# Sheet1.net
KiCad netlist of a schematic drawn in Altium Designer
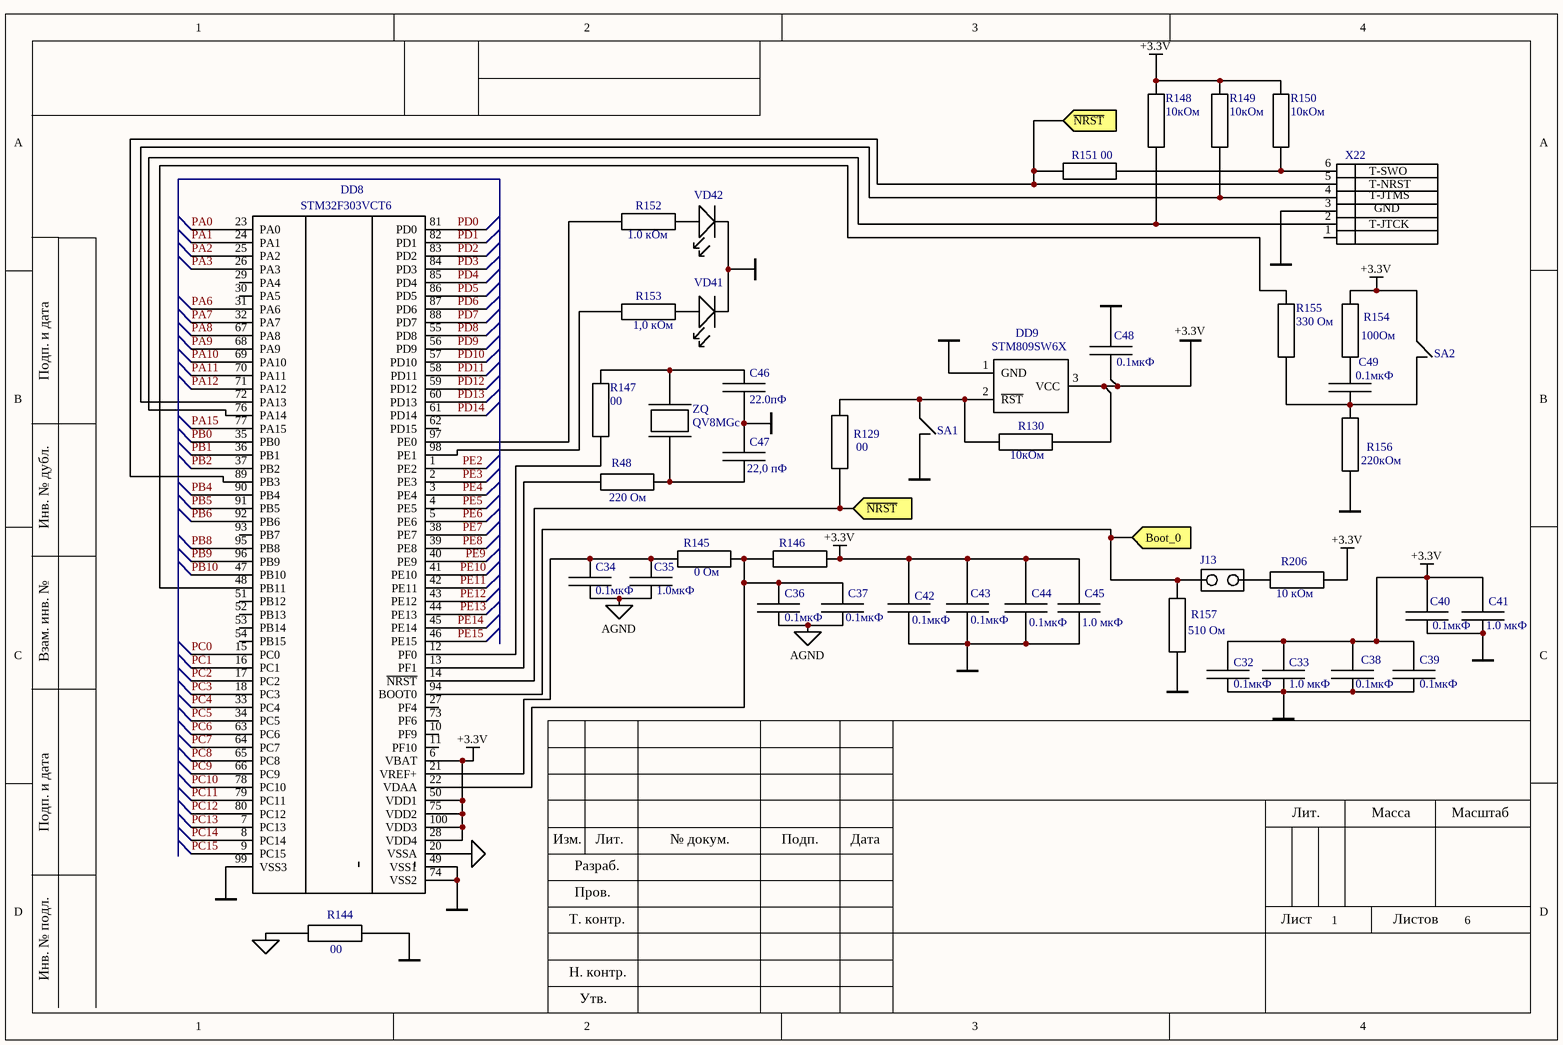
[diagram p0: Sheet1.SchDoc]

(export (version "E")
  (design (tool "Eeschema 10.0.6"))
  (components
    (comp (ref "C32")
      (value "C0805")
      (fields (field (name "ALTIUM_UNNAMED_1") "0.1мкФ"))
      (libsource (lib "Board_QFP") (part "C0805"))
    )
    (comp (ref "C33")
      (value "C0805")
      (fields (field (name "ALTIUM_UNNAMED_1") "1.0 мкФ"))
      (libsource (lib "Board_QFP") (part "C0805"))
    )
    (comp (ref "C34")
      (value "C0805")
      (fields (field (name "ALTIUM_UNNAMED_1") "0.1мкФ"))
      (libsource (lib "Board_QFP") (part "C0805"))
    )
    (comp (ref "C35")
      (value "C0805")
      (fields (field (name "ALTIUM_UNNAMED_1") "1.0мкФ"))
      (libsource (lib "Board_QFP") (part "C0805"))
    )
    (comp (ref "C36")
      (value "C0805")
      (fields (field (name "ALTIUM_UNNAMED_1") "0.1мкФ"))
      (libsource (lib "Board_QFP") (part "C0805"))
    )
    (comp (ref "C37")
      (value "C0805")
      (fields (field (name "ALTIUM_UNNAMED_1") "0.1мкФ"))
      (libsource (lib "Board_QFP") (part "C0805"))
    )
    (comp (ref "C38")
      (value "C0805")
      (fields (field (name "ALTIUM_UNNAMED_1") "0.1мкФ"))
      (libsource (lib "") (part "C0805_1"))
    )
    (comp (ref "C39")
      (value "C0805")
      (fields (field (name "ALTIUM_UNNAMED_1") "0.1мкФ"))
      (libsource (lib "Board_QFP") (part "C0805"))
    )
    (comp (ref "C40")
      (value "C0805")
      (fields (field (name "ALTIUM_UNNAMED_1") "0.1мкФ"))
      (libsource (lib "Board_QFP") (part "C0805"))
    )
    (comp (ref "C41")
      (value "C0805")
      (fields (field (name "ALTIUM_UNNAMED_1") "1.0 мкФ"))
      (libsource (lib "Board_QFP") (part "C0805"))
    )
    (comp (ref "C42")
      (value "C0805")
      (fields (field (name "ALTIUM_UNNAMED_1") "0.1мкФ"))
      (libsource (lib "Board_QFP") (part "C0805"))
    )
    (comp (ref "C43")
      (value "C0805")
      (fields (field (name "ALTIUM_UNNAMED_1") "0.1мкФ"))
      (libsource (lib "Board_QFP") (part "C0805"))
    )
    (comp (ref "C44")
      (value "C0805")
      (fields (field (name "ALTIUM_UNNAMED_1") "0.1мкФ"))
      (libsource (lib "Board_QFP") (part "C0805"))
    )
    (comp (ref "C45")
      (value "C0805")
      (fields (field (name "ALTIUM_UNNAMED_1") "1.0 мкФ"))
      (libsource (lib "Board_QFP") (part "C0805"))
    )
    (comp (ref "C46")
      (value "C0805")
      (fields (field (name "ALTIUM_UNNAMED_1") "22.0пФ"))
      (libsource (lib "Board_QFP") (part "C0805"))
    )
    (comp (ref "C47")
      (value "C0805")
      (fields (field (name "ALTIUM_UNNAMED_1") "22,0 пФ"))
      (libsource (lib "Board_QFP") (part "C0805"))
    )
    (comp (ref "C48")
      (value "C0805")
      (fields (field (name "ALTIUM_UNNAMED_1") "0.1мкФ"))
      (libsource (lib "Board_QFP") (part "C0805"))
    )
    (comp (ref "C49")
      (value "C0805")
      (fields (field (name "ALTIUM_UNNAMED_1") "0.1мкФ"))
      (libsource (lib "") (part "C0805_2"))
    )
    (comp (ref "DD8") (value "STM32F303VCT6") (libsource (lib "Board_QFP") (part "STM32F303VCT6")))
    (comp (ref "DD9") (value "STM809SW6X") (libsource (lib "Board_QFP") (part "STM809SW6X")))
    (comp (ref "J13") (value "jamp") (libsource (lib "Board_QFP") (part "jamp")))
    (comp (ref "R48")
      (value "R0805")
      (fields (field (name "ALTIUM_UNNAMED_1") "220 Ом"))
      (libsource (lib "Board_QFP") (part "R0805"))
    )
    (comp (ref "R129")
      (value "R0805")
      (fields (field (name "ALTIUM_UNNAMED_1") "00"))
      (libsource (lib "Board_QFP") (part "R0805"))
    )
    (comp (ref "R130")
      (value "R0805")
      (fields (field (name "ALTIUM_UNNAMED_1") "10кОм"))
      (libsource (lib "Board_QFP") (part "R0805"))
    )
    (comp (ref "R144")
      (value "R0805")
      (fields (field (name "ALTIUM_UNNAMED_1") "00"))
      (libsource (lib "Board_QFP") (part "R0805"))
    )
    (comp (ref "R145")
      (value "R0805")
      (fields (field (name "ALTIUM_UNNAMED_1") "0 Ом"))
      (libsource (lib "Board_QFP") (part "R0805"))
    )
    (comp (ref "R146") (value "R0805") (libsource (lib "Board_QFP") (part "R0805")))
    (comp (ref "R147")
      (value "R0805")
      (fields (field (name "ALTIUM_UNNAMED_1") "00"))
      (libsource (lib "Board_QFP") (part "R0805"))
    )
    (comp (ref "R148")
      (value "R0805")
      (fields (field (name "ALTIUM_UNNAMED_1") "10кОм"))
      (libsource (lib "Board_QFP") (part "R0805"))
    )
    (comp (ref "R149")
      (value "R0805")
      (fields (field (name "ALTIUM_UNNAMED_1") "10кОм"))
      (libsource (lib "") (part "R0805_1"))
    )
    (comp (ref "R150")
      (value "R0805")
      (fields (field (name "ALTIUM_UNNAMED_1") "10кОм"))
      (libsource (lib "") (part "R0805_1"))
    )
    (comp (ref "R151")
      (value "R0805")
      (fields (field (name "ALTIUM_UNNAMED_1") "00"))
      (libsource (lib "Board_QFP") (part "R0805"))
    )
    (comp (ref "R152")
      (value "R0805")
      (fields (field (name "ALTIUM_UNNAMED_1") "1.0 кОм"))
      (libsource (lib "Board_QFP") (part "R0805"))
    )
    (comp (ref "R153")
      (value "R0805")
      (fields (field (name "ALTIUM_UNNAMED_1") "1,0 кОм"))
      (libsource (lib "Board_QFP") (part "R0805"))
    )
    (comp (ref "R154")
      (value "R0805")
      (fields (field (name "ALTIUM_UNNAMED_1") "100Ом"))
      (libsource (lib "Board_QFP") (part "R0805"))
    )
    (comp (ref "R155")
      (value "R0805")
      (fields (field (name "ALTIUM_UNNAMED_1") "330 Ом"))
      (libsource (lib "") (part "R0805_1"))
    )
    (comp (ref "R156")
      (value "R0805")
      (fields (field (name "ALTIUM_UNNAMED_1") "220кОм"))
      (libsource (lib "Board_QFP") (part "R0805"))
    )
    (comp (ref "R157")
      (value "R0805")
      (fields (field (name "ALTIUM_UNNAMED_1") "510 Ом"))
      (libsource (lib "Board_QFP") (part "R0805"))
    )
    (comp (ref "R206")
      (value "R0805")
      (fields (field (name "ALTIUM_UNNAMED_1") "10 кОм"))
      (libsource (lib "Board_QFP") (part "R0805"))
    )
    (comp (ref "SA1") (value "SWT-1") (libsource (lib "Board_QFP") (part "SWT-1")))
    (comp (ref "SA2") (value "SWT-1") (libsource (lib "Board_QFP") (part "SWT-1")))
    (comp (ref "VD41") (value "LED") (libsource (lib "Board_QFP") (part "LED")))
    (comp (ref "VD42") (value "LED") (libsource (lib "Board_QFP") (part "LED")))
    (comp (ref "X22") (value "PLS-6") (libsource (lib "Board_QFP") (part "PLS-6")))
    (comp (ref "ZQ") (value "QV8MGc") (libsource (lib "Board_QFP") (part "QV8MGc")))
  )
  (nets
    (net (code "1") (name "+3.3V") (class "Default")
      (node (ref "C32") (pin "1") (pinfunction "1_1") (pintype "passive"))
      (node (ref "C33") (pin "1") (pinfunction "1_1") (pintype "passive"))
      (node (ref "C38") (pin "1") (pinfunction "1_1") (pintype "passive"))
      (node (ref "C39") (pin "1") (pinfunction "1_1") (pintype "passive"))
      (node (ref "C40") (pin "1") (pinfunction "1_1") (pintype "passive"))
      (node (ref "C41") (pin "1") (pinfunction "1_1") (pintype "passive"))
      (node (ref "C42") (pin "1") (pinfunction "1_1") (pintype "passive"))
      (node (ref "C43") (pin "1") (pinfunction "1_1") (pintype "passive"))
      (node (ref "C44") (pin "1") (pinfunction "1_1") (pintype "passive"))
      (node (ref "C45") (pin "1") (pinfunction "1_1") (pintype "passive"))
      (node (ref "C48") (pin "2") (pinfunction "2_2") (pintype "passive"))
      (node (ref "DD8") (pin "100") (pinfunction "VDD3_100") (pintype "passive"))
      (node (ref "DD8") (pin "28") (pinfunction "VDD4_28") (pintype "passive"))
      (node (ref "DD8") (pin "50") (pinfunction "VDD1_50") (pintype "passive"))
      (node (ref "DD8") (pin "6") (pinfunction "VBAT_6") (pintype "passive"))
      (node (ref "DD8") (pin "75") (pinfunction "VDD2_75") (pintype "passive"))
      (node (ref "DD9") (pin "3") (pinfunction "VCC_3") (pintype "passive"))
      (node (ref "R130") (pin "2") (pinfunction "2_2") (pintype "passive"))
      (node (ref "R146") (pin "2") (pinfunction "2_2") (pintype "passive"))
      (node (ref "R148") (pin "2") (pinfunction "2_2") (pintype "passive"))
      (node (ref "R149") (pin "2") (pinfunction "2_2") (pintype "passive"))
      (node (ref "R150") (pin "2") (pinfunction "2_2") (pintype "passive"))
      (node (ref "R154") (pin "2") (pinfunction "2_2") (pintype "passive"))
      (node (ref "R206") (pin "2") (pinfunction "2_2") (pintype "passive"))
      (node (ref "SA2") (pin "1") (pinfunction "1_1") (pintype "passive"))
    )
    (net (code "2") (name "/Boot_0") (class "Default")
      (node (ref "DD8") (pin "94") (pinfunction "BOOT0_94") (pintype "passive"))
      (node (ref "J13") (pin "1") (pinfunction "1_1") (pintype "passive"))
      (node (ref "R157") (pin "2") (pinfunction "2_2") (pintype "passive"))
    )
    (net (code "3") (name "/NRST") (class "Default")
      (node (ref "DD8") (pin "14") (pinfunction "NRST_14") (pintype "passive"))
      (node (ref "DD8") (pin "89") (pinfunction "PB3_89") (pintype "passive"))
      (node (ref "R129") (pin "1") (pinfunction "1_1") (pintype "passive"))
      (node (ref "R151") (pin "1") (pinfunction "1_1") (pintype "passive"))
      (node (ref "X22") (pin "5") (pinfunction "5_5") (pintype "passive"))
    )
    (net (code "4") (name "/PA0") (class "Default")
      (node (ref "DD8") (pin "23") (pinfunction "PA0_23") (pintype "passive"))
    )
    (net (code "5") (name "/PA1") (class "Default")
      (node (ref "DD8") (pin "24") (pinfunction "PA1_24") (pintype "passive"))
    )
    (net (code "6") (name "/PA2") (class "Default")
      (node (ref "DD8") (pin "25") (pinfunction "PA2_25") (pintype "passive"))
    )
    (net (code "7") (name "/PA3") (class "Default")
      (node (ref "DD8") (pin "26") (pinfunction "PA3_26") (pintype "passive"))
    )
    (net (code "8") (name "/PA6") (class "Default")
      (node (ref "DD8") (pin "31") (pinfunction "PA6_31") (pintype "passive"))
    )
    (net (code "9") (name "/PA7") (class "Default")
      (node (ref "DD8") (pin "32") (pinfunction "PA7_32") (pintype "passive"))
    )
    (net (code "10") (name "/PA8") (class "Default")
      (node (ref "DD8") (pin "67") (pinfunction "PA8_67") (pintype "passive"))
    )
    (net (code "11") (name "/PA9") (class "Default")
      (node (ref "DD8") (pin "68") (pinfunction "PA9_68") (pintype "passive"))
    )
    (net (code "12") (name "/PA10") (class "Default")
      (node (ref "DD8") (pin "69") (pinfunction "PA10_69") (pintype "passive"))
    )
    (net (code "13") (name "/PA11") (class "Default")
      (node (ref "DD8") (pin "70") (pinfunction "PA11_70") (pintype "passive"))
    )
    (net (code "14") (name "/PA12") (class "Default")
      (node (ref "DD8") (pin "71") (pinfunction "PA12_71") (pintype "passive"))
    )
    (net (code "15") (name "/PA15") (class "Default")
      (node (ref "DD8") (pin "77") (pinfunction "PA15_77") (pintype "passive"))
    )
    (net (code "16") (name "/PB0") (class "Default")
      (node (ref "DD8") (pin "35") (pinfunction "PB0_35") (pintype "passive"))
    )
    (net (code "17") (name "/PB1") (class "Default")
      (node (ref "DD8") (pin "36") (pinfunction "PB1_36") (pintype "passive"))
    )
    (net (code "18") (name "/PB2") (class "Default")
      (node (ref "DD8") (pin "37") (pinfunction "PB2_37") (pintype "passive"))
    )
    (net (code "19") (name "/PB4") (class "Default")
      (node (ref "DD8") (pin "90") (pinfunction "PB4_90") (pintype "passive"))
    )
    (net (code "20") (name "/PB5") (class "Default")
      (node (ref "DD8") (pin "91") (pinfunction "PB5_91") (pintype "passive"))
    )
    (net (code "21") (name "/PB6") (class "Default")
      (node (ref "DD8") (pin "92") (pinfunction "PB6_92") (pintype "passive"))
    )
    (net (code "22") (name "/PB8") (class "Default")
      (node (ref "DD8") (pin "95") (pinfunction "PB8_95") (pintype "passive"))
    )
    (net (code "23") (name "/PB9") (class "Default")
      (node (ref "DD8") (pin "96") (pinfunction "PB9_96") (pintype "passive"))
    )
    (net (code "24") (name "/PB10") (class "Default")
      (node (ref "DD8") (pin "47") (pinfunction "PB10_47") (pintype "passive"))
    )
    (net (code "25") (name "/PC0") (class "Default")
      (node (ref "DD8") (pin "15") (pinfunction "PC0_15") (pintype "passive"))
    )
    (net (code "26") (name "/PC1") (class "Default")
      (node (ref "DD8") (pin "16") (pinfunction "PC1_16") (pintype "passive"))
    )
    (net (code "27") (name "/PC2") (class "Default")
      (node (ref "DD8") (pin "17") (pinfunction "PC2_17") (pintype "passive"))
    )
    (net (code "28") (name "/PC3") (class "Default")
      (node (ref "DD8") (pin "18") (pinfunction "PC3_18") (pintype "passive"))
    )
    (net (code "29") (name "/PC4") (class "Default")
      (node (ref "DD8") (pin "33") (pinfunction "PC4_33") (pintype "passive"))
    )
    (net (code "30") (name "/PC5") (class "Default")
      (node (ref "DD8") (pin "34") (pinfunction "PC5_34") (pintype "passive"))
    )
    (net (code "31") (name "/PC6") (class "Default")
      (node (ref "DD8") (pin "63") (pinfunction "PC6_63") (pintype "passive"))
    )
    (net (code "32") (name "/PC7") (class "Default")
      (node (ref "DD8") (pin "64") (pinfunction "PC7_64") (pintype "passive"))
    )
    (net (code "33") (name "/PC8") (class "Default")
      (node (ref "DD8") (pin "65") (pinfunction "PC8_65") (pintype "passive"))
    )
    (net (code "34") (name "/PC9") (class "Default")
      (node (ref "DD8") (pin "66") (pinfunction "PC9_66") (pintype "passive"))
    )
    (net (code "35") (name "/PC10") (class "Default")
      (node (ref "DD8") (pin "78") (pinfunction "PC10_78") (pintype "passive"))
    )
    (net (code "36") (name "/PC11") (class "Default")
      (node (ref "DD8") (pin "79") (pinfunction "PC11_79") (pintype "passive"))
    )
    (net (code "37") (name "/PC12") (class "Default")
      (node (ref "DD8") (pin "80") (pinfunction "PC12_80") (pintype "passive"))
    )
    (net (code "38") (name "/PC13") (class "Default")
      (node (ref "DD8") (pin "7") (pinfunction "PC13_7") (pintype "passive"))
    )
    (net (code "39") (name "/PC14") (class "Default")
      (node (ref "DD8") (pin "8") (pinfunction "PC14_8") (pintype "passive"))
    )
    (net (code "40") (name "/PC15") (class "Default")
      (node (ref "DD8") (pin "9") (pinfunction "PC15_9") (pintype "passive"))
    )
    (net (code "41") (name "/PD0") (class "Default")
      (node (ref "DD8") (pin "81") (pinfunction "PD0_81") (pintype "passive"))
    )
    (net (code "42") (name "/PD1") (class "Default")
      (node (ref "DD8") (pin "82") (pinfunction "PD1_82") (pintype "passive"))
    )
    (net (code "43") (name "/PD2") (class "Default")
      (node (ref "DD8") (pin "83") (pinfunction "PD2_83") (pintype "passive"))
    )
    (net (code "44") (name "/PD3") (class "Default")
      (node (ref "DD8") (pin "84") (pinfunction "PD3_84") (pintype "passive"))
    )
    (net (code "45") (name "/PD4") (class "Default")
      (node (ref "DD8") (pin "85") (pinfunction "PD4_85") (pintype "passive"))
    )
    (net (code "46") (name "/PD5") (class "Default")
      (node (ref "DD8") (pin "86") (pinfunction "PD5_86") (pintype "passive"))
    )
    (net (code "47") (name "/PD6") (class "Default")
      (node (ref "DD8") (pin "87") (pinfunction "PD6_87") (pintype "passive"))
    )
    (net (code "48") (name "/PD7") (class "Default")
      (node (ref "DD8") (pin "88") (pinfunction "PD7_88") (pintype "passive"))
    )
    (net (code "49") (name "/PD8") (class "Default")
      (node (ref "DD8") (pin "55") (pinfunction "PD8_55") (pintype "passive"))
    )
    (net (code "50") (name "/PD9") (class "Default")
      (node (ref "DD8") (pin "56") (pinfunction "PD9_56") (pintype "passive"))
    )
    (net (code "51") (name "/PD10") (class "Default")
      (node (ref "DD8") (pin "57") (pinfunction "PD10_57") (pintype "passive"))
    )
    (net (code "52") (name "/PD11") (class "Default")
      (node (ref "DD8") (pin "58") (pinfunction "PD11_58") (pintype "passive"))
    )
    (net (code "53") (name "/PD12") (class "Default")
      (node (ref "DD8") (pin "59") (pinfunction "PD12_59") (pintype "passive"))
    )
    (net (code "54") (name "/PD13") (class "Default")
      (node (ref "DD8") (pin "60") (pinfunction "PD13_60") (pintype "passive"))
    )
    (net (code "55") (name "/PD14") (class "Default")
      (node (ref "DD8") (pin "61") (pinfunction "PD14_61") (pintype "passive"))
    )
    (net (code "56") (name "/PE2") (class "Default")
      (node (ref "DD8") (pin "1") (pinfunction "PE2_1") (pintype "passive"))
    )
    (net (code "57") (name "/PE3") (class "Default")
      (node (ref "DD8") (pin "2") (pinfunction "PE3_2") (pintype "passive"))
    )
    (net (code "58") (name "/PE4") (class "Default")
      (node (ref "DD8") (pin "3") (pinfunction "PE4_3") (pintype "passive"))
    )
    (net (code "59") (name "/PE5") (class "Default")
      (node (ref "DD8") (pin "4") (pinfunction "PE5_4") (pintype "passive"))
    )
    (net (code "60") (name "/PE6") (class "Default")
      (node (ref "DD8") (pin "5") (pinfunction "PE6_5") (pintype "passive"))
    )
    (net (code "61") (name "/PE7") (class "Default")
      (node (ref "DD8") (pin "38") (pinfunction "PE7_38") (pintype "passive"))
    )
    (net (code "62") (name "/PE8") (class "Default")
      (node (ref "DD8") (pin "39") (pinfunction "PE8_39") (pintype "passive"))
    )
    (net (code "63") (name "/PE9") (class "Default")
      (node (ref "DD8") (pin "40") (pinfunction "PE9_40") (pintype "passive"))
    )
    (net (code "64") (name "/PE10") (class "Default")
      (node (ref "DD8") (pin "41") (pinfunction "PE10_41") (pintype "passive"))
    )
    (net (code "65") (name "/PE11") (class "Default")
      (node (ref "DD8") (pin "42") (pinfunction "PE11_42") (pintype "passive"))
    )
    (net (code "66") (name "/PE12") (class "Default")
      (node (ref "DD8") (pin "43") (pinfunction "PE12_43") (pintype "passive"))
    )
    (net (code "67") (name "/PE13") (class "Default")
      (node (ref "DD8") (pin "44") (pinfunction "PE13_44") (pintype "passive"))
    )
    (net (code "68") (name "/PE14") (class "Default")
      (node (ref "DD8") (pin "45") (pinfunction "PE14_45") (pintype "passive"))
    )
    (net (code "69") (name "/PE15") (class "Default")
      (node (ref "DD8") (pin "46") (pinfunction "PE15_46") (pintype "passive"))
    )
    (net (code "70") (name "AGND") (class "Default")
      (node (ref "C34") (pin "2") (pinfunction "2_2") (pintype "passive"))
      (node (ref "C35") (pin "2") (pinfunction "2_2") (pintype "passive"))
      (node (ref "C36") (pin "2") (pinfunction "2_2") (pintype "passive"))
      (node (ref "C37") (pin "2") (pinfunction "2_2") (pintype "passive"))
      (node (ref "DD8") (pin "20") (pinfunction "VSSA_20") (pintype "passive"))
      (node (ref "R144") (pin "1") (pinfunction "1_1") (pintype "passive"))
    )
    (net (code "71") (name "GND") (class "Default")
      (node (ref "C32") (pin "2") (pinfunction "2_2") (pintype "passive"))
      (node (ref "C33") (pin "2") (pinfunction "2_2") (pintype "passive"))
      (node (ref "C38") (pin "2") (pinfunction "2_2") (pintype "passive"))
      (node (ref "C39") (pin "2") (pinfunction "2_2") (pintype "passive"))
      (node (ref "C40") (pin "2") (pinfunction "2_2") (pintype "passive"))
      (node (ref "C41") (pin "2") (pinfunction "2_2") (pintype "passive"))
      (node (ref "C42") (pin "2") (pinfunction "2_2") (pintype "passive"))
      (node (ref "C43") (pin "2") (pinfunction "2_2") (pintype "passive"))
      (node (ref "C44") (pin "2") (pinfunction "2_2") (pintype "passive"))
      (node (ref "C45") (pin "2") (pinfunction "2_2") (pintype "passive"))
      (node (ref "C46") (pin "1") (pinfunction "1_1") (pintype "passive"))
      (node (ref "C47") (pin "2") (pinfunction "2_2") (pintype "passive"))
      (node (ref "C48") (pin "1") (pinfunction "1_1") (pintype "passive"))
      (node (ref "DD8") (pin "49") (pinfunction "VSS1_49") (pintype "passive"))
      (node (ref "DD8") (pin "74") (pinfunction "VSS2_74") (pintype "passive"))
      (node (ref "DD8") (pin "99") (pinfunction "VSS3_99") (pintype "passive"))
      (node (ref "DD9") (pin "1") (pinfunction "GND_1") (pintype "passive"))
      (node (ref "R144") (pin "2") (pinfunction "2_2") (pintype "passive"))
      (node (ref "R156") (pin "1") (pinfunction "1_1") (pintype "passive"))
      (node (ref "R157") (pin "1") (pinfunction "1_1") (pintype "passive"))
      (node (ref "SA1") (pin "2") (pinfunction "2_2") (pintype "passive"))
      (node (ref "VD41") (pin "1") (pinfunction "A_1") (pintype "passive"))
      (node (ref "VD42") (pin "1") (pinfunction "A_1") (pintype "passive"))
      (node (ref "X22") (pin "3") (pinfunction "3_3") (pintype "passive"))
    )
    (net (code "72") (name "Net-(C46-Pad2)") (class "Default")
      (node (ref "C46") (pin "2") (pinfunction "2_2") (pintype "passive"))
      (node (ref "R147") (pin "2") (pinfunction "2_2") (pintype "passive"))
      (node (ref "ZQ") (pin "2") (pinfunction "2_2") (pintype "passive"))
    )
    (net (code "73") (name "Net-(C47-Pad1)") (class "Default")
      (node (ref "C47") (pin "1") (pinfunction "1_1") (pintype "passive"))
      (node (ref "R48") (pin "2") (pinfunction "2_2") (pintype "passive"))
      (node (ref "ZQ") (pin "1") (pinfunction "1_1") (pintype "passive"))
    )
    (net (code "74") (name "Net-(C49-Pad1)") (class "Default")
      (node (ref "C49") (pin "1") (pinfunction "1_1") (pintype "passive"))
      (node (ref "R155") (pin "1") (pinfunction "1_1") (pintype "passive"))
      (node (ref "R156") (pin "2") (pinfunction "2_2") (pintype "passive"))
      (node (ref "SA2") (pin "2") (pinfunction "2_2") (pintype "passive"))
    )
    (net (code "75") (name "Net-(C49-Pad2)") (class "Default")
      (node (ref "C49") (pin "2") (pinfunction "2_2") (pintype "passive"))
      (node (ref "R154") (pin "1") (pinfunction "1_1") (pintype "passive"))
    )
    (net (code "76") (name "Net-(DD8-PA13)") (class "Default")
      (node (ref "DD8") (pin "72") (pinfunction "PA13_72") (pintype "passive"))
      (node (ref "R149") (pin "1") (pinfunction "1_1") (pintype "passive"))
      (node (ref "X22") (pin "4") (pinfunction "4_4") (pintype "passive"))
    )
    (net (code "77") (name "Net-(DD8-PA14)") (class "Default")
      (node (ref "DD8") (pin "76") (pinfunction "PA14_76") (pintype "passive"))
      (node (ref "R148") (pin "1") (pinfunction "1_1") (pintype "passive"))
      (node (ref "X22") (pin "2") (pinfunction "2_2") (pintype "passive"))
    )
    (net (code "78") (name "Net-(DD8-PB11)") (class "Default")
      (node (ref "DD8") (pin "48") (pinfunction "PB11_48") (pintype "passive"))
      (node (ref "R155") (pin "2") (pinfunction "2_2") (pintype "passive"))
    )
    (net (code "79") (name "Net-(DD8-PE0)") (class "Default")
      (node (ref "DD8") (pin "97") (pinfunction "PE0_97") (pintype "passive"))
      (node (ref "R152") (pin "1") (pinfunction "1_1") (pintype "passive"))
    )
    (net (code "80") (name "Net-(DD8-PE1)") (class "Default")
      (node (ref "DD8") (pin "98") (pinfunction "PE1_98") (pintype "passive"))
      (node (ref "R153") (pin "1") (pinfunction "1_1") (pintype "passive"))
    )
    (net (code "81") (name "Net-(DD8-PF0)") (class "Default")
      (node (ref "DD8") (pin "12") (pinfunction "PF0_12") (pintype "passive"))
      (node (ref "R147") (pin "1") (pinfunction "1_1") (pintype "passive"))
    )
    (net (code "82") (name "Net-(DD8-PF1)") (class "Default")
      (node (ref "DD8") (pin "13") (pinfunction "PF1_13") (pintype "passive"))
      (node (ref "R48") (pin "1") (pinfunction "1_1") (pintype "passive"))
    )
    (net (code "83") (name "Net-(DD8-VDAA)") (class "Default")
      (node (ref "C36") (pin "1") (pinfunction "1_1") (pintype "passive"))
      (node (ref "C37") (pin "1") (pinfunction "1_1") (pintype "passive"))
      (node (ref "DD8") (pin "22") (pinfunction "VDAA_22") (pintype "passive"))
      (node (ref "R145") (pin "2") (pinfunction "2_2") (pintype "passive"))
      (node (ref "R146") (pin "1") (pinfunction "1_1") (pintype "passive"))
    )
    (net (code "84") (name "Net-(DD8-VREF+)") (class "Default")
      (node (ref "C34") (pin "1") (pinfunction "1_1") (pintype "passive"))
      (node (ref "C35") (pin "1") (pinfunction "1_1") (pintype "passive"))
      (node (ref "DD8") (pin "21") (pinfunction "VREF+_21") (pintype "passive"))
      (node (ref "R145") (pin "1") (pinfunction "1_1") (pintype "passive"))
    )
    (net (code "85") (name "Net-(DD9-RST)") (class "Default")
      (node (ref "DD9") (pin "2") (pinfunction "RST_2") (pintype "passive"))
      (node (ref "R129") (pin "2") (pinfunction "2_2") (pintype "passive"))
      (node (ref "R130") (pin "1") (pinfunction "1_1") (pintype "passive"))
      (node (ref "SA1") (pin "1") (pinfunction "1_1") (pintype "passive"))
    )
    (net (code "86") (name "Net-(J13-Pad2)") (class "Default")
      (node (ref "J13") (pin "2") (pinfunction "2_2") (pintype "passive"))
      (node (ref "R206") (pin "1") (pinfunction "1_1") (pintype "passive"))
    )
    (net (code "87") (name "Net-(R150-Pad1)") (class "Default")
      (node (ref "R150") (pin "1") (pinfunction "1_1") (pintype "passive"))
      (node (ref "R151") (pin "2") (pinfunction "2_2") (pintype "passive"))
      (node (ref "X22") (pin "6") (pinfunction "6_6") (pintype "passive"))
    )
    (net (code "88") (name "unconnected-(DD8-PA4-Pad29)") (class "Default")
      (node (ref "DD8") (pin "29") (pinfunction "PA4_29") (pintype "passive"))
    )
    (net (code "89") (name "unconnected-(DD8-PA5-Pad30)") (class "Default")
      (node (ref "DD8") (pin "30") (pinfunction "PA5_30") (pintype "passive"))
    )
    (net (code "90") (name "unconnected-(DD8-PB7-Pad93)") (class "Default")
      (node (ref "DD8") (pin "93") (pinfunction "PB7_93") (pintype "passive"))
    )
    (net (code "91") (name "unconnected-(DD8-PB12-Pad51)") (class "Default")
      (node (ref "DD8") (pin "51") (pinfunction "PB12_51") (pintype "passive"))
    )
    (net (code "92") (name "unconnected-(DD8-PB13-Pad52)") (class "Default")
      (node (ref "DD8") (pin "52") (pinfunction "PB13_52") (pintype "passive"))
    )
    (net (code "93") (name "unconnected-(DD8-PB14-Pad53)") (class "Default")
      (node (ref "DD8") (pin "53") (pinfunction "PB14_53") (pintype "passive"))
    )
    (net (code "94") (name "unconnected-(DD8-PB15-Pad54)") (class "Default")
      (node (ref "DD8") (pin "54") (pinfunction "PB15_54") (pintype "passive"))
    )
    (net (code "95") (name "unconnected-(DD8-PD15-Pad62)") (class "Default")
      (node (ref "DD8") (pin "62") (pinfunction "PD15_62") (pintype "passive"))
    )
    (net (code "96") (name "unconnected-(DD8-PF4-Pad27)") (class "Default")
      (node (ref "DD8") (pin "27") (pinfunction "PF4_27") (pintype "passive"))
    )
    (net (code "97") (name "unconnected-(DD8-PF6-Pad73)") (class "Default")
      (node (ref "DD8") (pin "73") (pinfunction "PF6_73") (pintype "passive"))
    )
    (net (code "98") (name "unconnected-(DD8-PF9-Pad10)") (class "Default")
      (node (ref "DD8") (pin "10") (pinfunction "PF9_10") (pintype "passive"))
    )
    (net (code "99") (name "unconnected-(DD8-PF10-Pad11)") (class "Default")
      (node (ref "DD8") (pin "11") (pinfunction "PF10_11") (pintype "passive"))
    )
    (net (code "100") (name "unconnected-(R152-Pad2)") (class "Default")
      (node (ref "R152") (pin "2") (pinfunction "2_2") (pintype "passive"))
    )
    (net (code "101") (name "unconnected-(R153-Pad2)") (class "Default")
      (node (ref "R153") (pin "2") (pinfunction "2_2") (pintype "passive"))
    )
    (net (code "102") (name "unconnected-(VD41-K-Pad2)") (class "Default")
      (node (ref "VD41") (pin "2") (pinfunction "K_2") (pintype "passive"))
    )
    (net (code "103") (name "unconnected-(VD42-K-Pad2)") (class "Default")
      (node (ref "VD42") (pin "2") (pinfunction "K_2") (pintype "passive"))
    )
    (net (code "104") (name "unconnected-(X22-Pad1)") (class "Default")
      (node (ref "X22") (pin "1") (pinfunction "1_1") (pintype "passive"))
    )
  )
)
